# shield_ESP.net
KiCad netlist of a schematic drawn in EAGLE
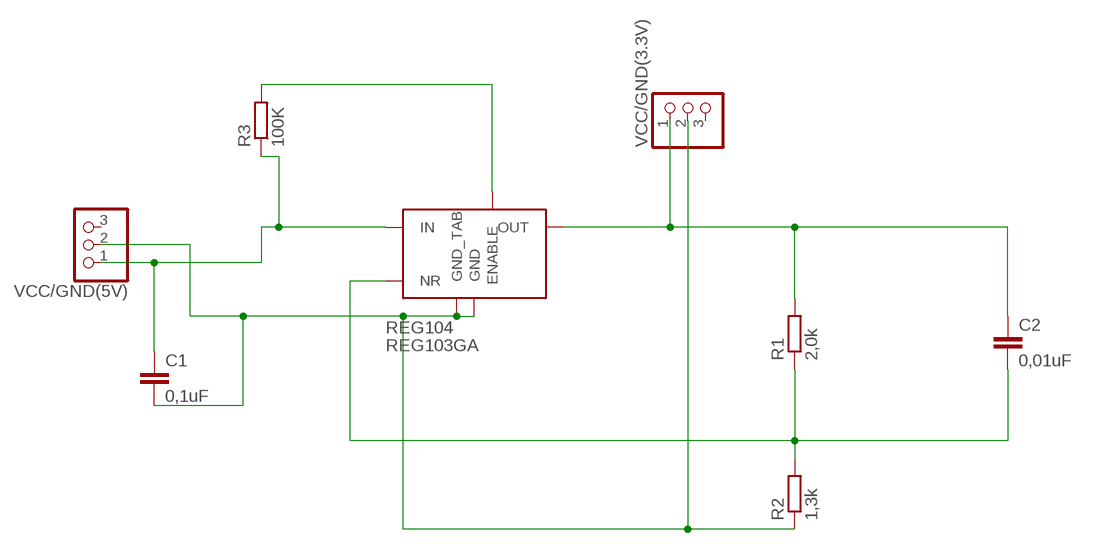
[diagram p0: schematic, sheet 1]

(export (version "E")
  (design (tool "Eeschema 10.0.6"))
  (components
    (comp (ref "C1")
      (value "0,1uF")
      (footprint "eagle-import:C025-025X050")
      (libsource (lib "eagle-import") (part "C-EU025-025X050"))
    )
    (comp (ref "C2")
      (value "0,01uF")
      (footprint "eagle-import:C025-025X050")
      (libsource (lib "eagle-import") (part "C-EU025-025X050"))
    )
    (comp (ref "R1")
      (value "2,0k")
      (footprint "eagle-import:0207_7")
      (libsource (lib "eagle-import") (part "R-EU_0207/7"))
    )
    (comp (ref "R2")
      (value "1,3k")
      (footprint "eagle-import:0207_7")
      (libsource (lib "eagle-import") (part "R-EU_0207/7"))
    )
    (comp (ref "R3")
      (value "100K")
      (footprint "eagle-import:0207_7")
      (libsource (lib "eagle-import") (part "R-EU_0207/7"))
    )
    (comp (ref "REG104")
      (value "REG103GA")
      (footprint "eagle-import:SOT223-5")
      (libsource (lib "eagle-import") (part "REG103GA"))
    )
    (comp (ref "VCC/GND(3.3V)")
      (value "PINHD-1X3/90")
      (footprint "eagle-import:1X03_90")
      (libsource (lib "eagle-import") (part "PINHD-1X3/90"))
    )
    (comp (ref "VCC/GND(5V)")
      (value "PINHD-1X3/90")
      (footprint "eagle-import:1X03_90")
      (libsource (lib "eagle-import") (part "PINHD-1X3/90"))
    )
  )
  (nets
    (net (code "1") (name "Net-(REG104-ENABLE)") (class "Default")
      (node (ref "R3") (pin "2") (pinfunction "2_2") (pintype "passive"))
      (node (ref "REG104") (pin "5") (pinfunction "ENABLE_5") (pintype "bidirectional"))
    )
    (net (code "2") (name "Net-(REG104-GND)") (class "Default")
      (node (ref "C1") (pin "2") (pinfunction "2_2") (pintype "passive"))
      (node (ref "R2") (pin "1") (pinfunction "1_1") (pintype "passive"))
      (node (ref "REG104") (pin "3") (pinfunction "GND_3") (pintype "bidirectional"))
      (node (ref "REG104") (pin "TAB") (pinfunction "GND_TAB_TAB") (pintype "bidirectional"))
      (node (ref "VCC/GND(3.3V)") (pin "2") (pinfunction "2_2") (pintype "passive"))
      (node (ref "VCC/GND(5V)") (pin "2") (pinfunction "2_2") (pintype "passive"))
    )
    (net (code "3") (name "Net-(REG104-IN)") (class "Default")
      (node (ref "C1") (pin "1") (pinfunction "1_1") (pintype "passive"))
      (node (ref "R3") (pin "1") (pinfunction "1_1") (pintype "passive"))
      (node (ref "REG104") (pin "1") (pinfunction "IN_1") (pintype "bidirectional"))
      (node (ref "VCC/GND(5V)") (pin "1") (pinfunction "1_1") (pintype "passive"))
    )
    (net (code "4") (name "Net-(REG104-NR)") (class "Default")
      (node (ref "C2") (pin "2") (pinfunction "2_2") (pintype "passive"))
      (node (ref "R1") (pin "1") (pinfunction "1_1") (pintype "passive"))
      (node (ref "R2") (pin "2") (pinfunction "2_2") (pintype "passive"))
      (node (ref "REG104") (pin "4") (pinfunction "NR_4") (pintype "bidirectional"))
    )
    (net (code "5") (name "Net-(REG104-OUT)") (class "Default")
      (node (ref "C2") (pin "1") (pinfunction "1_1") (pintype "passive"))
      (node (ref "R1") (pin "2") (pinfunction "2_2") (pintype "passive"))
      (node (ref "REG104") (pin "2") (pinfunction "OUT_2") (pintype "bidirectional"))
      (node (ref "VCC/GND(3.3V)") (pin "1") (pinfunction "1_1") (pintype "passive"))
    )
    (net (code "6") (name "unconnected-(VCC/GND(3.3V)-Pad3)") (class "Default")
      (node (ref "VCC/GND(3.3V)") (pin "3") (pinfunction "3_3") (pintype "passive"))
    )
    (net (code "7") (name "unconnected-(VCC/GND(5V)-Pad3)") (class "Default")
      (node (ref "VCC/GND(5V)") (pin "3") (pinfunction "3_3") (pintype "passive"))
    )
  )
)
